# 17_-_HDMI_IN.net
KiCad netlist of a schematic drawn in Altium Designer
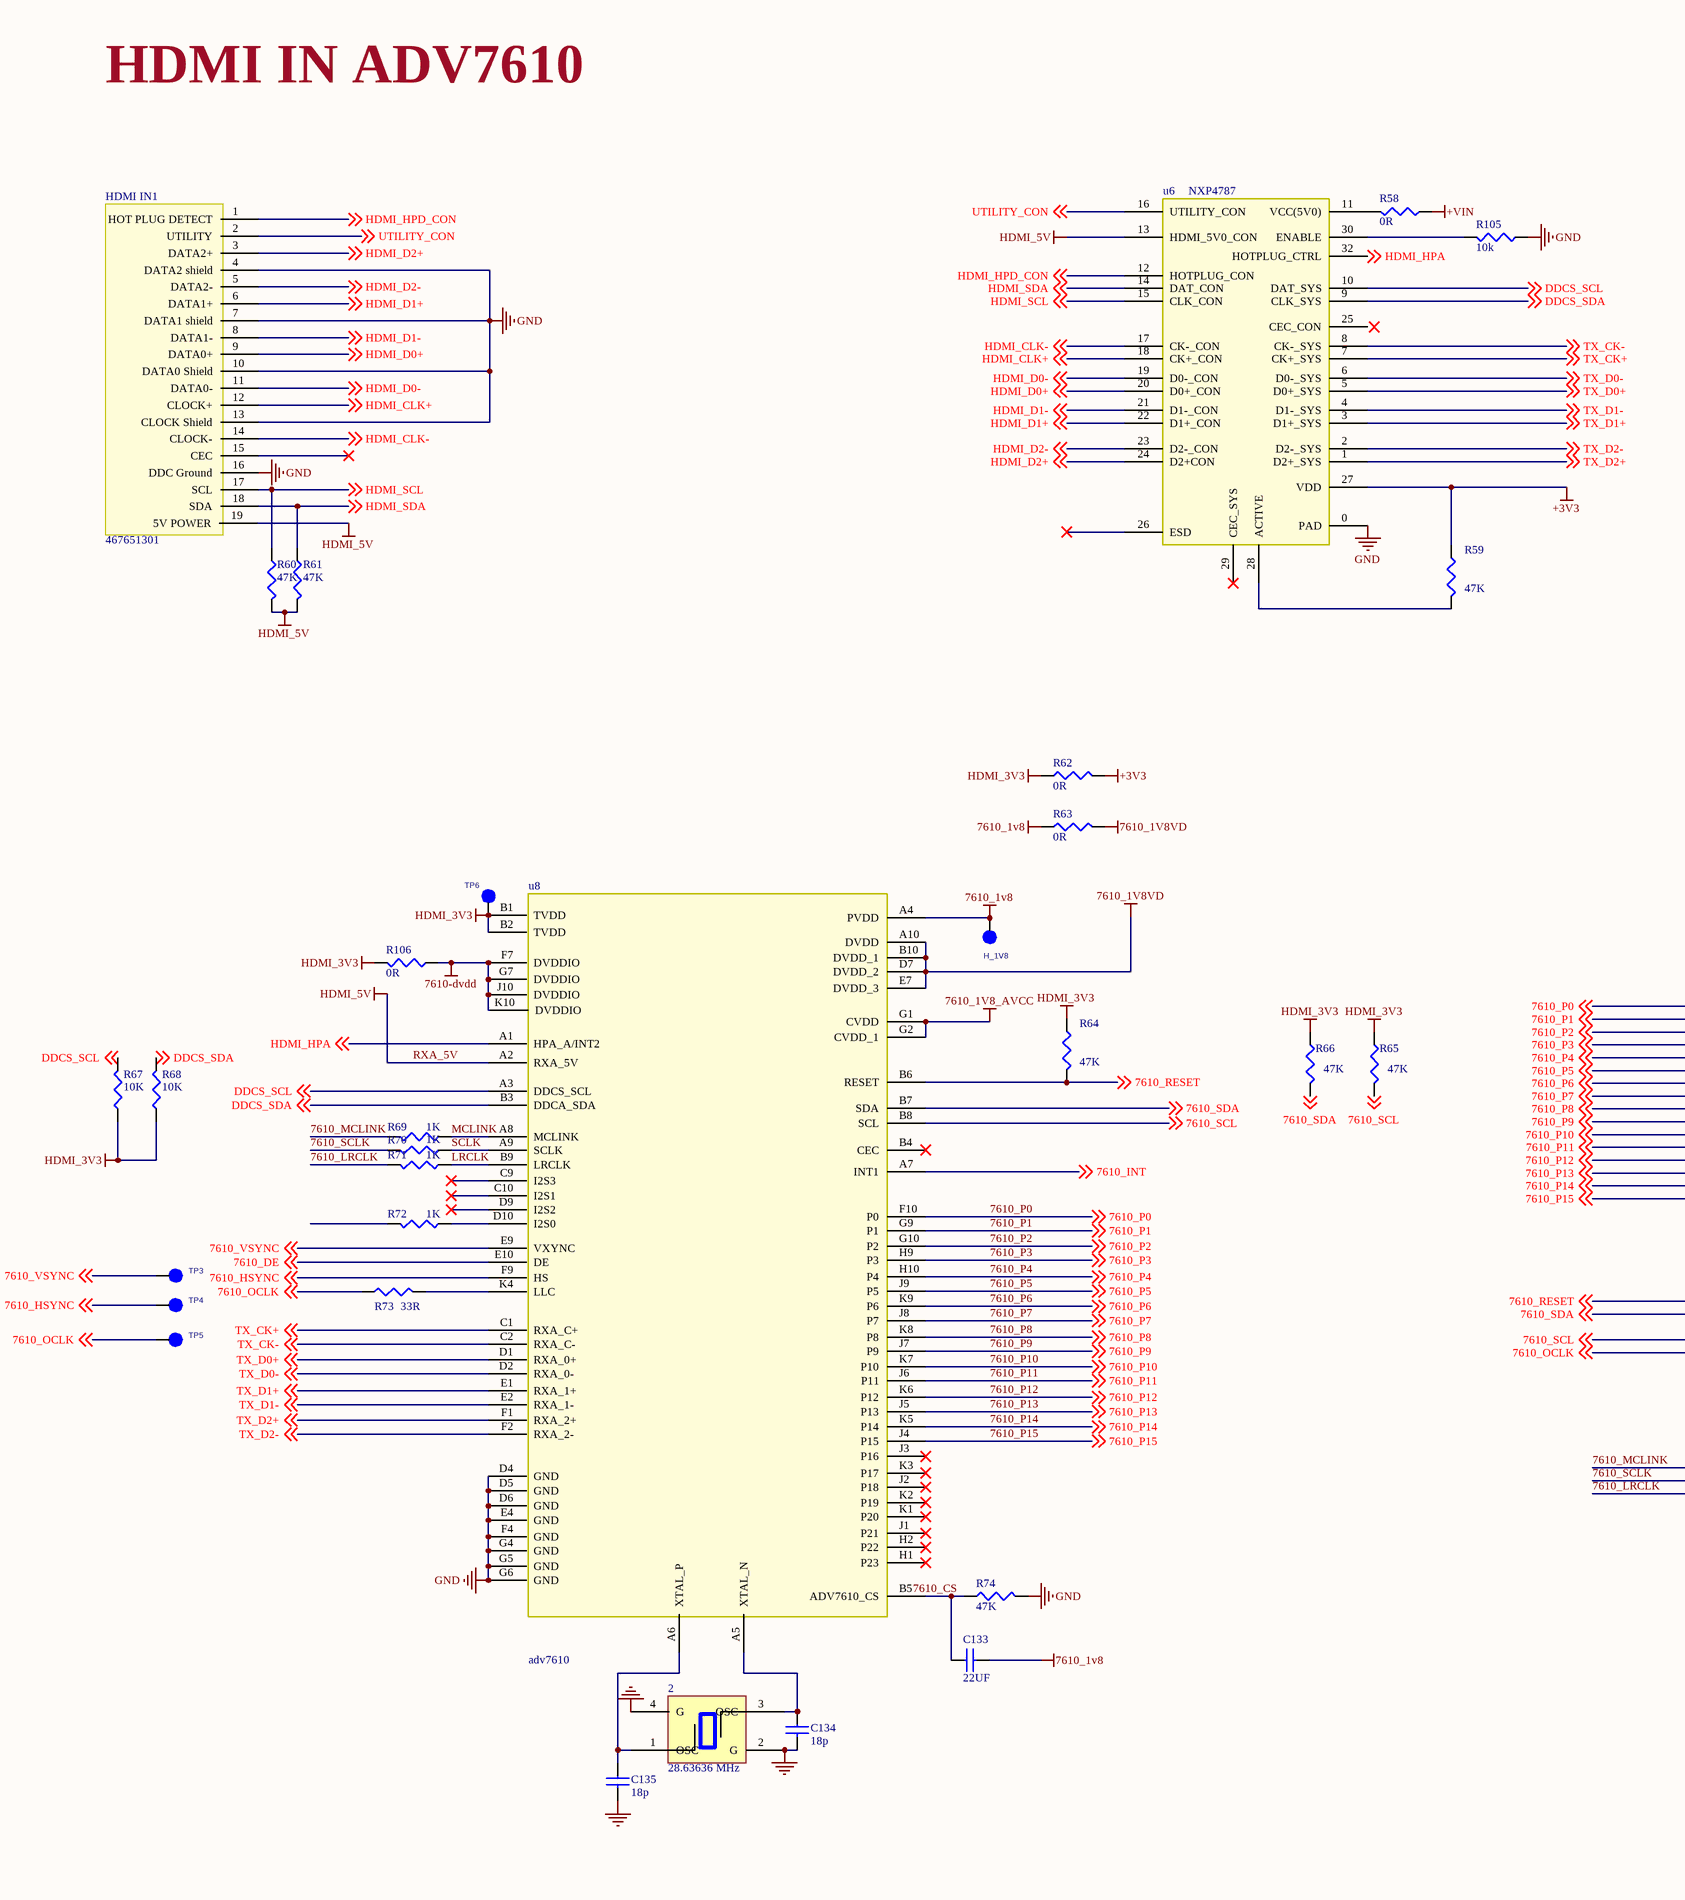
[diagram p0: [17] - HDMI_IN.SchDoc, left]
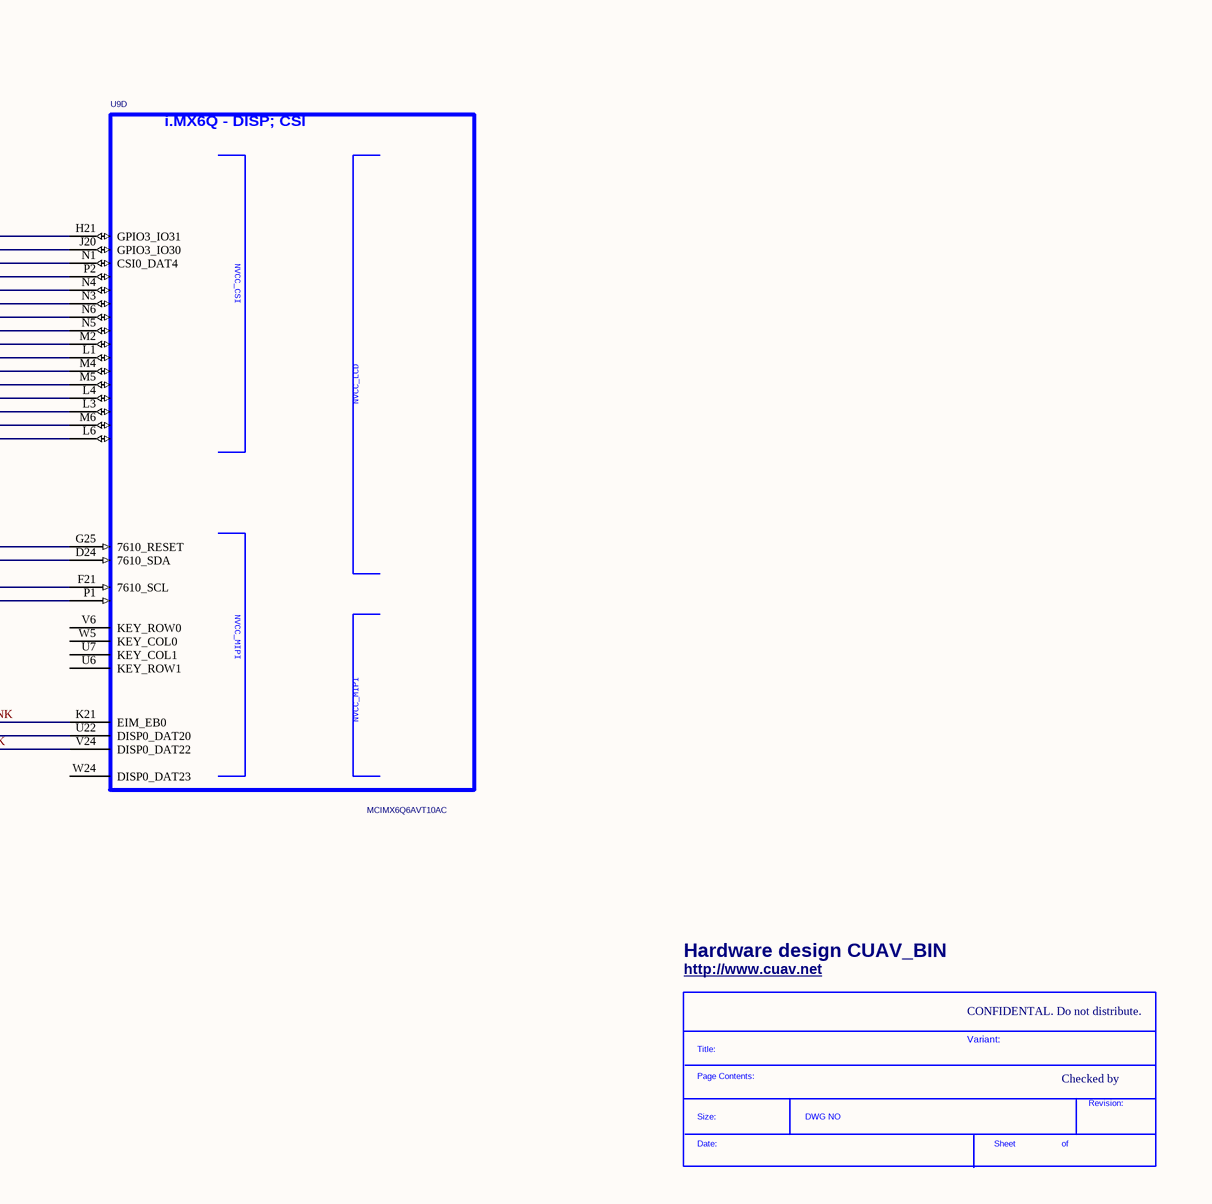
[diagram p1: [17] - HDMI_IN.SchDoc, right]

(export (version "E")
  (design (tool "Eeschema 10.0.6"))
  (components
    (comp (ref "*") (value "SDTitleBlock") (libsource (lib "*") (part "SDTitleBlock")))
    (comp (ref "2") (value "28.63636 MHz") (footprint "TSX-3225") (libsource (lib "hack") (part "TSX-3225")))
    (comp (ref "C133")
      (value "22UF")
      (footprint "0603C")
      (description "CAP CER 18PF 50V C0G 5% 0402")
      (fields
        (field (name "MANUFACTURER") "TDK Corporation")
        (field (name "MANUFACTURER PART NUMBER") "C1005C0G1H180J")
      )
      (libsource (lib "Integrated_Library_RF_FEB_2012") (part "C1005C0G1H180J"))
    )
    (comp (ref "C134")
      (value "18p")
      (footprint "0402cap")
      (description "CAP CER 18PF 50V C0G 5% 0402")
      (fields
        (field (name "MANUFACTURER") "TDK Corporation")
        (field (name "MANUFACTURER PART NUMBER") "C1005C0G1H180J")
      )
      (libsource (lib "Integrated_Library_RF_FEB_2012") (part "C1005C0G1H180J"))
    )
    (comp (ref "C135")
      (value "18p")
      (footprint "0402cap")
      (description "CAP CER 18PF 50V C0G 5% 0402")
      (fields
        (field (name "MANUFACTURER") "TDK Corporation")
        (field (name "MANUFACTURER PART NUMBER") "C1005C0G1H180J")
      )
      (libsource (lib "Integrated_Library_RF_FEB_2012") (part "C1005C0G1H180J"))
    )
    (comp (ref "HDMI IN1")
      (value "467651301")
      (footprint "467651301")
      (libsource (lib "hack") (part "467651301"))
    )
    (comp (ref "H_1V8")
      (value "H_3V3")
      (description "TEST POINT PAD 0.5MM DIA SMT, NO PART TO ORDER")
      (libsource (lib "*") (part "TESTLOOP"))
    )
    (comp (ref "R58")
      (value "0R")
      (footprint "R0402")
      (description "RES 1.00 OHM 1/16W 1% 0402 SM")
      (fields
        (field (name "MANUFACTURER") "Yageo")
        (field (name "MANUFACTURER PART NUMBER") "RC0402FR-071RL")
      )
      (libsource (lib "Integrated_Library_RF_FEB_2012") (part "RC0402FR-071RL"))
    )
    (comp (ref "R59")
      (value "47K")
      (footprint "R0402")
      (description "RES 1.00 OHM 1/16W 1% 0402 SM")
      (fields
        (field (name "MANUFACTURER") "Yageo")
        (field (name "MANUFACTURER PART NUMBER") "RC0402FR-071RL")
      )
      (libsource (lib "Integrated_Library_RF_FEB_2012") (part "RC0402FR-071RL"))
    )
    (comp (ref "R60")
      (value "47K")
      (footprint "R0402")
      (description "RES 1.00 OHM 1/16W 1% 0402 SM")
      (fields
        (field (name "MANUFACTURER") "Yageo")
        (field (name "MANUFACTURER PART NUMBER") "RC0402FR-071RL")
      )
      (libsource (lib "Integrated_Library_RF_FEB_2012") (part "RC0402FR-071RL"))
    )
    (comp (ref "R61")
      (value "47K")
      (footprint "R0402")
      (description "RES 1.00 OHM 1/16W 1% 0402 SM")
      (fields
        (field (name "MANUFACTURER") "Yageo")
        (field (name "MANUFACTURER PART NUMBER") "RC0402FR-071RL")
      )
      (libsource (lib "Integrated_Library_RF_FEB_2012") (part "RC0402FR-071RL"))
    )
    (comp (ref "R62")
      (value "0R")
      (footprint "R0402")
      (description "RES 1.00 OHM 1/16W 1% 0402 SM")
      (fields
        (field (name "MANUFACTURER") "Yageo")
        (field (name "MANUFACTURER PART NUMBER") "RC0402FR-071RL")
      )
      (libsource (lib "Integrated_Library_RF_FEB_2012") (part "RC0402FR-071RL"))
    )
    (comp (ref "R63")
      (value "0R")
      (footprint "R0402")
      (description "RES 1.00 OHM 1/16W 1% 0402 SM")
      (fields
        (field (name "MANUFACTURER") "Yageo")
        (field (name "MANUFACTURER PART NUMBER") "RC0402FR-071RL")
      )
      (libsource (lib "Integrated_Library_RF_FEB_2012") (part "RC0402FR-071RL"))
    )
    (comp (ref "R64")
      (value "47K")
      (footprint "R0402")
      (description "RES 1.00 OHM 1/16W 1% 0402 SM")
      (fields
        (field (name "MANUFACTURER") "Yageo")
        (field (name "MANUFACTURER PART NUMBER") "RC0402FR-071RL")
      )
      (libsource (lib "Integrated_Library_RF_FEB_2012") (part "RC0402FR-071RL"))
    )
    (comp (ref "R65")
      (value "47K")
      (footprint "R0402")
      (description "RES 39.0K OHM 1/16W 1% 0402 SMD")
      (fields
        (field (name "MANUFACTURER") "Yageo")
        (field (name "MANUFACTURER PART NUMBER") "RC0402FR-0739KL")
      )
      (libsource (lib "Integrated_Library_RF_FEB_2012") (part "RC0402FR-0739KL"))
    )
    (comp (ref "R66")
      (value "47K")
      (footprint "R0402")
      (description "RES 39.0K OHM 1/16W 1% 0402 SMD")
      (fields
        (field (name "MANUFACTURER") "Yageo")
        (field (name "MANUFACTURER PART NUMBER") "RC0402FR-0739KL")
      )
      (libsource (lib "Integrated_Library_RF_FEB_2012") (part "RC0402FR-0739KL"))
    )
    (comp (ref "R67")
      (value "10K")
      (footprint "R0402")
      (description "RES 1.00 OHM 1/16W 1% 0402 SM")
      (fields
        (field (name "MANUFACTURER") "Yageo")
        (field (name "MANUFACTURER PART NUMBER") "RC0402FR-071RL")
      )
      (libsource (lib "Integrated_Library_RF_FEB_2012") (part "RC0402FR-071RL"))
    )
    (comp (ref "R68")
      (value "10K")
      (footprint "R0402")
      (description "RES 1.00 OHM 1/16W 1% 0402 SM")
      (fields
        (field (name "MANUFACTURER") "Yageo")
        (field (name "MANUFACTURER PART NUMBER") "RC0402FR-071RL")
      )
      (libsource (lib "Integrated_Library_RF_FEB_2012") (part "RC0402FR-071RL"))
    )
    (comp (ref "R69")
      (value "1K")
      (footprint "R0402")
      (description "RES 1.00 OHM 1/16W 1% 0402 SM")
      (fields
        (field (name "MANUFACTURER") "Yageo")
        (field (name "MANUFACTURER PART NUMBER") "RC0402FR-071RL")
      )
      (libsource (lib "Integrated_Library_RF_FEB_2012") (part "RC0402FR-071RL"))
    )
    (comp (ref "R70")
      (value "1K")
      (footprint "R0402")
      (description "RES 1.00 OHM 1/16W 1% 0402 SM")
      (fields
        (field (name "MANUFACTURER") "Yageo")
        (field (name "MANUFACTURER PART NUMBER") "RC0402FR-071RL")
      )
      (libsource (lib "Integrated_Library_RF_FEB_2012") (part "RC0402FR-071RL"))
    )
    (comp (ref "R71")
      (value "1K")
      (footprint "R0402")
      (description "RES 1.00 OHM 1/16W 1% 0402 SM")
      (fields
        (field (name "MANUFACTURER") "Yageo")
        (field (name "MANUFACTURER PART NUMBER") "RC0402FR-071RL")
      )
      (libsource (lib "Integrated_Library_RF_FEB_2012") (part "RC0402FR-071RL"))
    )
    (comp (ref "R72")
      (value "1K")
      (footprint "R0402")
      (description "RES 1.00 OHM 1/16W 1% 0402 SM")
      (fields
        (field (name "MANUFACTURER") "Yageo")
        (field (name "MANUFACTURER PART NUMBER") "RC0402FR-071RL")
      )
      (libsource (lib "Integrated_Library_RF_FEB_2012") (part "RC0402FR-071RL"))
    )
    (comp (ref "R73")
      (value "33R")
      (footprint "R0402")
      (description "RES 1.00 OHM 1/16W 1% 0402 SM")
      (fields
        (field (name "MANUFACTURER") "Yageo")
        (field (name "MANUFACTURER PART NUMBER") "RC0402FR-071RL")
      )
      (libsource (lib "Integrated_Library_RF_FEB_2012") (part "RC0402FR-071RL"))
    )
    (comp (ref "R74")
      (value "47K")
      (footprint "R0402")
      (description "RES 1.00 OHM 1/16W 1% 0402 SM")
      (fields
        (field (name "MANUFACTURER") "Yageo")
        (field (name "MANUFACTURER PART NUMBER") "RC0402FR-071RL")
      )
      (libsource (lib "Integrated_Library_RF_FEB_2012") (part "RC0402FR-071RL"))
    )
    (comp (ref "R105")
      (value "10k")
      (footprint "R0402")
      (description "RES 1.00 OHM 1/16W 1% 0402 SM")
      (fields
        (field (name "MANUFACTURER") "Yageo")
        (field (name "MANUFACTURER PART NUMBER") "RC0402FR-071RL")
      )
      (libsource (lib "Integrated_Library_RF_FEB_2012") (part "RC0402FR-071RL"))
    )
    (comp (ref "R106")
      (value "0R")
      (footprint "R0402")
      (description "RES 1.00 OHM 1/16W 1% 0402 SM")
      (fields
        (field (name "MANUFACTURER") "Yageo")
        (field (name "MANUFACTURER PART NUMBER") "RC0402FR-071RL")
      )
      (libsource (lib "Integrated_Library_RF_FEB_2012") (part "RC0402FR-071RL"))
    )
    (comp (ref "TP3")
      (value "7610_VSYNC")
      (description "TEST POINT PAD 0.5MM DIA SMT, NO PART TO ORDER")
      (libsource (lib "*") (part "TESTLOOP"))
    )
    (comp (ref "TP4")
      (value "7610_HSYNC")
      (description "TEST POINT PAD 0.5MM DIA SMT, NO PART TO ORDER")
      (libsource (lib "*") (part "TESTLOOP"))
    )
    (comp (ref "TP5")
      (value "tpad_020")
      (description "TEST POINT PAD 0.5MM DIA SMT, NO PART TO ORDER")
      (libsource (lib "*") (part "TESTLOOP"))
    )
    (comp (ref "TP6")
      (value "H_3V3")
      (description "TEST POINT PAD 0.5MM DIA SMT, NO PART TO ORDER")
      (libsource (lib "*") (part "TESTLOOP"))
    )
    (comp (ref "u6") (value "NXP4787") (footprint "QFN32_1") (libsource (lib "hack") (part "NXP4787")))
    (comp (ref "u8") (value "adv7610") (footprint "BC-76") (libsource (lib "hack") (part "adv7610")))
    (comp (ref "U9")
      (value "MCIMX6Q6AVT10AC")
      (description "IC MCU MX6QUAD ARM CORTEX-A9 FCPBGA624")
      (libsource (lib "*") (part "PCIMX6Q6VV1A"))
    )
  )
  (nets
    (net (code "1") (name "+3V3") (class "Default")
      (node (ref "R59") (pin "1") (pinfunction "1_1") (pintype "passive"))
      (node (ref "R62") (pin "2") (pinfunction "2_2") (pintype "passive"))
      (node (ref "u6") (pin "27") (pinfunction "VDD_27") (pintype "passive"))
    )
    (net (code "2") (name "+VIN") (class "Default")
      (node (ref "R58") (pin "1") (pinfunction "1_1") (pintype "passive"))
    )
    (net (code "4") (name "/7610_LRCLK") (class "Default")
      (node (ref "R71") (pin "2") (pinfunction "2_2") (pintype "passive"))
      (node (ref "U9") (pin "V24") (pinfunction "DISP0_DAT22_V24") (pintype "passive"))
    )
    (net (code "5") (name "/7610_MCLINK") (class "Default")
      (node (ref "R69") (pin "2") (pinfunction "2_2") (pintype "passive"))
      (node (ref "U9") (pin "K21") (pinfunction "EIM_EB0_K21") (pintype "passive"))
    )
    (net (code "6") (name "/7610_SCLK") (class "Default")
      (node (ref "R70") (pin "2") (pinfunction "2_2") (pintype "passive"))
      (node (ref "U9") (pin "U22") (pinfunction "DISP0_DAT20_U22") (pintype "passive"))
    )
    (net (code "7") (name "/LRCLK") (class "Default")
      (node (ref "R71") (pin "1") (pinfunction "1_1") (pintype "passive"))
      (node (ref "u8") (pin "B9") (pinfunction "LRCLK_B9") (pintype "passive"))
    )
    (net (code "8") (name "/MCLINK") (class "Default")
      (node (ref "R69") (pin "1") (pinfunction "1_1") (pintype "passive"))
      (node (ref "u8") (pin "A8") (pinfunction "MCLINK_A8") (pintype "passive"))
    )
    (net (code "9") (name "/SCLK") (class "Default")
      (node (ref "R70") (pin "1") (pinfunction "1_1") (pintype "passive"))
      (node (ref "u8") (pin "A9") (pinfunction "SCLK_A9") (pintype "passive"))
    )
    (net (code "10") (name "7610-dvdd") (class "Default")
      (node (ref "R106") (pin "1") (pinfunction "1_1") (pintype "passive"))
      (node (ref "u8") (pin "F7") (pinfunction "DVDDIO_F7") (pintype "passive"))
      (node (ref "u8") (pin "G7") (pinfunction "DVDDIO_G7") (pintype "passive"))
      (node (ref "u8") (pin "J10") (pinfunction "DVDDIO_J10") (pintype "passive"))
      (node (ref "u8") (pin "K10") (pinfunction "DVDDIO_K10") (pintype "passive"))
    )
    (net (code "11") (name "7610_1V8VD") (class "Default")
      (node (ref "R63") (pin "2") (pinfunction "2_2") (pintype "passive"))
      (node (ref "u8") (pin "A10") (pinfunction "DVDD_A10") (pintype "passive"))
      (node (ref "u8") (pin "B10") (pinfunction "DVDD_1_B10") (pintype "passive"))
      (node (ref "u8") (pin "D7") (pinfunction "DVDD_2_D7") (pintype "passive"))
      (node (ref "u8") (pin "E7") (pinfunction "DVDD_3_E7") (pintype "passive"))
    )
    (net (code "12") (name "7610_1V8_AVCC") (class "Default")
      (node (ref "u8") (pin "G1") (pinfunction "CVDD_G1") (pintype "passive"))
      (node (ref "u8") (pin "G2") (pinfunction "CVDD_1_G2") (pintype "passive"))
    )
    (net (code "13") (name "7610_1v8") (class "Default")
      (node (ref "C133") (pin "2") (pinfunction "2_2") (pintype "passive"))
      (node (ref "H_1V8") (pin "1") (pinfunction "Pin1_1") (pintype "passive"))
      (node (ref "R63") (pin "1") (pinfunction "1_1") (pintype "passive"))
      (node (ref "u8") (pin "A4") (pinfunction "PVDD_A4") (pintype "passive"))
    )
    (net (code "14") (name "7610_DE") (class "Default")
      (node (ref "u8") (pin "E10") (pinfunction "DE_E10") (pintype "passive"))
    )
    (net (code "15") (name "7610_HSYNC") (class "Default")
      (node (ref "TP4") (pin "1") (pinfunction "Pin1_1") (pintype "passive"))
      (node (ref "u8") (pin "F9") (pinfunction "HS_F9") (pintype "passive"))
    )
    (net (code "16") (name "7610_INT") (class "Default")
      (node (ref "u8") (pin "A7") (pinfunction "INT1_A7") (pintype "passive"))
    )
    (net (code "17") (name "7610_OCLK") (class "Default")
      (node (ref "R73") (pin "1") (pinfunction "1_1") (pintype "passive"))
      (node (ref "TP5") (pin "1") (pinfunction "Pin1_1") (pintype "passive"))
      (node (ref "U9") (pin "P1") (pintype "input"))
    )
    (net (code "18") (name "7610_P0") (class "Default")
      (node (ref "U9") (pin "H21") (pinfunction "GPIO3_IO31_H21") (pintype "bidirectional"))
      (node (ref "u8") (pin "F10") (pinfunction "P0_F10") (pintype "passive"))
    )
    (net (code "19") (name "7610_P1") (class "Default")
      (node (ref "U9") (pin "J20") (pinfunction "GPIO3_IO30_J20") (pintype "bidirectional"))
      (node (ref "u8") (pin "G9") (pinfunction "P1_G9") (pintype "passive"))
    )
    (net (code "20") (name "7610_P2") (class "Default")
      (node (ref "U9") (pin "N1") (pinfunction "CSI0_DAT4_N1") (pintype "bidirectional"))
      (node (ref "u8") (pin "G10") (pinfunction "P2_G10") (pintype "passive"))
    )
    (net (code "21") (name "7610_P3") (class "Default")
      (node (ref "U9") (pin "P2") (pintype "bidirectional"))
      (node (ref "u8") (pin "H9") (pinfunction "P3_H9") (pintype "passive"))
    )
    (net (code "22") (name "7610_P4") (class "Default")
      (node (ref "U9") (pin "N4") (pintype "bidirectional"))
      (node (ref "u8") (pin "H10") (pinfunction "P4_H10") (pintype "passive"))
    )
    (net (code "23") (name "7610_P5") (class "Default")
      (node (ref "U9") (pin "N3") (pintype "bidirectional"))
      (node (ref "u8") (pin "J9") (pinfunction "P5_J9") (pintype "passive"))
    )
    (net (code "24") (name "7610_P6") (class "Default")
      (node (ref "U9") (pin "N6") (pintype "bidirectional"))
      (node (ref "u8") (pin "K9") (pinfunction "P6_K9") (pintype "passive"))
    )
    (net (code "25") (name "7610_P7") (class "Default")
      (node (ref "U9") (pin "N5") (pintype "bidirectional"))
      (node (ref "u8") (pin "J8") (pinfunction "P7_J8") (pintype "passive"))
    )
    (net (code "26") (name "7610_P8") (class "Default")
      (node (ref "U9") (pin "M2") (pintype "bidirectional"))
      (node (ref "u8") (pin "K8") (pinfunction "P8_K8") (pintype "passive"))
    )
    (net (code "27") (name "7610_P9") (class "Default")
      (node (ref "U9") (pin "L1") (pintype "bidirectional"))
      (node (ref "u8") (pin "J7") (pinfunction "P9_J7") (pintype "passive"))
    )
    (net (code "28") (name "7610_P10") (class "Default")
      (node (ref "U9") (pin "M4") (pintype "bidirectional"))
      (node (ref "u8") (pin "K7") (pinfunction "P10_K7") (pintype "passive"))
    )
    (net (code "29") (name "7610_P11") (class "Default")
      (node (ref "U9") (pin "M5") (pintype "bidirectional"))
      (node (ref "u8") (pin "J6") (pinfunction "P11_J6") (pintype "passive"))
    )
    (net (code "30") (name "7610_P12") (class "Default")
      (node (ref "U9") (pin "L4") (pintype "bidirectional"))
      (node (ref "u8") (pin "K6") (pinfunction "P12_K6") (pintype "passive"))
    )
    (net (code "31") (name "7610_P13") (class "Default")
      (node (ref "U9") (pin "L3") (pintype "bidirectional"))
      (node (ref "u8") (pin "J5") (pinfunction "P13_J5") (pintype "passive"))
    )
    (net (code "32") (name "7610_P14") (class "Default")
      (node (ref "U9") (pin "M6") (pintype "bidirectional"))
      (node (ref "u8") (pin "K5") (pinfunction "P14_K5") (pintype "passive"))
    )
    (net (code "33") (name "7610_P15") (class "Default")
      (node (ref "U9") (pin "L6") (pintype "bidirectional"))
      (node (ref "u8") (pin "J4") (pinfunction "P15_J4") (pintype "passive"))
    )
    (net (code "34") (name "7610_RESET") (class "Default")
      (node (ref "R64") (pin "2") (pinfunction "2_2") (pintype "passive"))
      (node (ref "U9") (pin "G25") (pinfunction "7610_RESET_G25") (pintype "input"))
      (node (ref "u8") (pin "B6") (pinfunction "RESET_B6") (pintype "passive"))
    )
    (net (code "35") (name "7610_SCL") (class "Default")
      (node (ref "R65") (pin "2") (pinfunction "2_2") (pintype "passive"))
      (node (ref "U9") (pin "F21") (pinfunction "7610_SCL_F21") (pintype "input"))
      (node (ref "u8") (pin "B8") (pinfunction "SCL_B8") (pintype "passive"))
    )
    (net (code "36") (name "7610_SDA") (class "Default")
      (node (ref "R66") (pin "2") (pinfunction "2_2") (pintype "passive"))
      (node (ref "U9") (pin "D24") (pinfunction "7610_SDA_D24") (pintype "input"))
      (node (ref "u8") (pin "B7") (pinfunction "SDA_B7") (pintype "passive"))
    )
    (net (code "37") (name "7610_VSYNC") (class "Default")
      (node (ref "TP3") (pin "1") (pinfunction "Pin1_1") (pintype "passive"))
      (node (ref "u8") (pin "E9") (pinfunction "VXYNC_E9") (pintype "passive"))
    )
    (net (code "38") (name "DDCS_SCL") (class "Default")
      (node (ref "R67") (pin "2") (pinfunction "2_2") (pintype "passive"))
      (node (ref "u6") (pin "10") (pinfunction "DAT_SYS_10") (pintype "passive"))
      (node (ref "u8") (pin "A3") (pinfunction "DDCS_SCL_A3") (pintype "passive"))
    )
    (net (code "39") (name "DDCS_SDA") (class "Default")
      (node (ref "R68") (pin "2") (pinfunction "2_2") (pintype "passive"))
      (node (ref "u6") (pin "9") (pinfunction "CLK_SYS_9") (pintype "passive"))
      (node (ref "u8") (pin "B3") (pinfunction "DDCA_SDA_B3") (pintype "passive"))
    )
    (net (code "40") (name "GND") (class "Default")
      (node (ref "2") (pin "2") (pinfunction "G_2") (pintype "passive"))
      (node (ref "2") (pin "4") (pinfunction "G_4") (pintype "passive"))
      (node (ref "C134") (pin "2") (pinfunction "2_2") (pintype "passive"))
      (node (ref "C135") (pin "2") (pinfunction "2_2") (pintype "passive"))
      (node (ref "HDMI IN1") (pin "10") (pinfunction "DATA0_Shield_10") (pintype "passive"))
      (node (ref "HDMI IN1") (pin "13") (pinfunction "CLOCK_Shield_13") (pintype "passive"))
      (node (ref "HDMI IN1") (pin "16") (pinfunction "DDC_Ground_16") (pintype "passive"))
      (node (ref "HDMI IN1") (pin "4") (pinfunction "DATA2_shield_4") (pintype "passive"))
      (node (ref "HDMI IN1") (pin "7") (pinfunction "DATA1_shield_7") (pintype "passive"))
      (node (ref "R105") (pin "1") (pinfunction "1_1") (pintype "passive"))
      (node (ref "R74") (pin "2") (pinfunction "2_2") (pintype "passive"))
      (node (ref "u6") (pin "0") (pinfunction "PAD_0") (pintype "passive"))
      (node (ref "u8") (pin "D4") (pinfunction "GND_D4") (pintype "passive"))
      (node (ref "u8") (pin "D5") (pinfunction "GND_D5") (pintype "passive"))
      (node (ref "u8") (pin "D6") (pinfunction "GND_D6") (pintype "passive"))
      (node (ref "u8") (pin "E4") (pinfunction "GND_E4") (pintype "passive"))
      (node (ref "u8") (pin "F4") (pinfunction "GND_F4") (pintype "passive"))
      (node (ref "u8") (pin "G4") (pinfunction "GND_G4") (pintype "passive"))
      (node (ref "u8") (pin "G5") (pinfunction "GND_G5") (pintype "passive"))
      (node (ref "u8") (pin "G6") (pinfunction "GND_G6") (pintype "passive"))
    )
    (net (code "41") (name "HDMI_3V3") (class "Default")
      (node (ref "R106") (pin "2") (pinfunction "2_2") (pintype "passive"))
      (node (ref "R62") (pin "1") (pinfunction "1_1") (pintype "passive"))
      (node (ref "R64") (pin "1") (pinfunction "1_1") (pintype "passive"))
      (node (ref "R65") (pin "1") (pinfunction "1_1") (pintype "passive"))
      (node (ref "R66") (pin "1") (pinfunction "1_1") (pintype "passive"))
      (node (ref "R67") (pin "1") (pinfunction "1_1") (pintype "passive"))
      (node (ref "R68") (pin "1") (pinfunction "1_1") (pintype "passive"))
      (node (ref "TP6") (pin "1") (pinfunction "Pin1_1") (pintype "passive"))
      (node (ref "u8") (pin "B1") (pinfunction "TVDD_B1") (pintype "passive"))
      (node (ref "u8") (pin "B2") (pinfunction "TVDD_B2") (pintype "passive"))
    )
    (net (code "42") (name "HDMI_5V") (class "Default")
      (node (ref "HDMI IN1") (pin "19") (pinfunction "5V_POWER_19") (pintype "passive"))
      (node (ref "R60") (pin "2") (pinfunction "2_2") (pintype "passive"))
      (node (ref "R61") (pin "2") (pinfunction "2_2") (pintype "passive"))
      (node (ref "u6") (pin "13") (pinfunction "HDMI_5V0_CON_13") (pintype "passive"))
      (node (ref "u8") (pin "A2") (pinfunction "RXA_5V_A2") (pintype "passive"))
    )
    (net (code "43") (name "HDMI_CLK+") (class "Default")
      (node (ref "HDMI IN1") (pin "12") (pinfunction "CLOCK+_12") (pintype "passive"))
      (node (ref "u6") (pin "18") (pinfunction "CK+_CON_18") (pintype "passive"))
    )
    (net (code "44") (name "HDMI_CLK-") (class "Default")
      (node (ref "HDMI IN1") (pin "14") (pinfunction "CLOCK-_14") (pintype "passive"))
      (node (ref "u6") (pin "17") (pinfunction "CK-_CON_17") (pintype "passive"))
    )
    (net (code "45") (name "HDMI_D0+") (class "Default")
      (node (ref "HDMI IN1") (pin "9") (pinfunction "DATA0+_9") (pintype "passive"))
      (node (ref "u6") (pin "20") (pinfunction "D0+_CON_20") (pintype "passive"))
    )
    (net (code "46") (name "HDMI_D0-") (class "Default")
      (node (ref "HDMI IN1") (pin "11") (pinfunction "DATA0-_11") (pintype "passive"))
      (node (ref "u6") (pin "19") (pinfunction "D0-_CON_19") (pintype "passive"))
    )
    (net (code "47") (name "HDMI_D1+") (class "Default")
      (node (ref "HDMI IN1") (pin "6") (pinfunction "DATA1+_6") (pintype "passive"))
      (node (ref "u6") (pin "22") (pinfunction "D1+_CON_22") (pintype "passive"))
    )
    (net (code "48") (name "HDMI_D1-") (class "Default")
      (node (ref "HDMI IN1") (pin "8") (pinfunction "DATA1-_8") (pintype "passive"))
      (node (ref "u6") (pin "21") (pinfunction "D1-_CON_21") (pintype "passive"))
    )
    (net (code "49") (name "HDMI_D2+") (class "Default")
      (node (ref "HDMI IN1") (pin "3") (pinfunction "DATA2+_3") (pintype "passive"))
      (node (ref "u6") (pin "24") (pinfunction "D2+CON_24") (pintype "passive"))
    )
    (net (code "50") (name "HDMI_D2-") (class "Default")
      (node (ref "HDMI IN1") (pin "5") (pinfunction "DATA2-_5") (pintype "passive"))
      (node (ref "u6") (pin "23") (pinfunction "D2-_CON_23") (pintype "passive"))
    )
    (net (code "51") (name "HDMI_HPA") (class "Default")
      (node (ref "u6") (pin "32") (pinfunction "HOTPLUG_CTRL_32") (pintype "passive"))
      (node (ref "u8") (pin "A1") (pinfunction "HPA_A/INT2_A1") (pintype "passive"))
    )
    (net (code "52") (name "HDMI_HPD_CON") (class "Default")
      (node (ref "HDMI IN1") (pin "1") (pinfunction "HOT_PLUG_DETECT_1") (pintype "passive"))
      (node (ref "u6") (pin "12") (pinfunction "HOTPLUG_CON_12") (pintype "passive"))
    )
    (net (code "53") (name "HDMI_SCL") (class "Default")
      (node (ref "HDMI IN1") (pin "17") (pinfunction "SCL_17") (pintype "passive"))
      (node (ref "R60") (pin "1") (pinfunction "1_1") (pintype "passive"))
      (node (ref "u6") (pin "15") (pinfunction "CLK_CON_15") (pintype "passive"))
    )
    (net (code "54") (name "HDMI_SDA") (class "Default")
      (node (ref "HDMI IN1") (pin "18") (pinfunction "SDA_18") (pintype "passive"))
      (node (ref "R61") (pin "1") (pinfunction "1_1") (pintype "passive"))
      (node (ref "u6") (pin "14") (pinfunction "DAT_CON_14") (pintype "passive"))
    )
    (net (code "55") (name "Net-(u6-ACTIVE)") (class "Default")
      (node (ref "R59") (pin "2") (pinfunction "2_2") (pintype "passive"))
      (node (ref "u6") (pin "28") (pinfunction "ACTIVE_28") (pintype "passive"))
    )
    (net (code "56") (name "Net-(u6-ENABLE)") (class "Default")
      (node (ref "R105") (pin "2") (pinfunction "2_2") (pintype "passive"))
      (node (ref "u6") (pin "30") (pinfunction "ENABLE_30") (pintype "passive"))
    )
    (net (code "57") (name "Net-(u6-VCC(5V0))") (class "Default")
      (node (ref "R58") (pin "2") (pinfunction "2_2") (pintype "passive"))
      (node (ref "u6") (pin "11") (pinfunction "VCC(5V0)_11") (pintype "passive"))
    )
    (net (code "58") (name "Net-(u8-ADV7610_CS)") (class "Default")
      (node (ref "C133") (pin "1") (pinfunction "1_1") (pintype "passive"))
      (node (ref "R74") (pin "1") (pinfunction "1_1") (pintype "passive"))
      (node (ref "u8") (pin "B5") (pinfunction "ADV7610_CS_B5") (pintype "passive"))
    )
    (net (code "59") (name "Net-(u8-I2S0)") (class "Default")
      (node (ref "R72") (pin "1") (pinfunction "1_1") (pintype "passive"))
      (node (ref "u8") (pin "D10") (pinfunction "I2S0_D10") (pintype "passive"))
    )
    (net (code "60") (name "Net-(u8-LLC)") (class "Default")
      (node (ref "R73") (pin "2") (pinfunction "2_2") (pintype "passive"))
      (node (ref "u8") (pin "K4") (pinfunction "LLC_K4") (pintype "passive"))
    )
    (net (code "61") (name "Net-(u8-XTAL_N)") (class "Default")
      (node (ref "2") (pin "3") (pinfunction "OSC_3") (pintype "passive"))
      (node (ref "C134") (pin "1") (pinfunction "1_1") (pintype "passive"))
      (node (ref "u8") (pin "A5") (pinfunction "XTAL_N_A5") (pintype "passive"))
    )
    (net (code "62") (name "Net-(u8-XTAL_P)") (class "Default")
      (node (ref "2") (pin "1") (pinfunction "OSC_1") (pintype "passive"))
      (node (ref "C135") (pin "1") (pinfunction "1_1") (pintype "passive"))
      (node (ref "u8") (pin "A6") (pinfunction "XTAL_P_A6") (pintype "passive"))
    )
    (net (code "63") (name "TX_CK+") (class "Default")
      (node (ref "u6") (pin "7") (pinfunction "CK+_SYS_7") (pintype "passive"))
      (node (ref "u8") (pin "C1") (pinfunction "RXA_C+_C1") (pintype "passive"))
    )
    (net (code "64") (name "TX_CK-") (class "Default")
      (node (ref "u6") (pin "8") (pinfunction "CK-_SYS_8") (pintype "passive"))
      (node (ref "u8") (pin "C2") (pinfunction "RXA_C-_C2") (pintype "passive"))
    )
    (net (code "65") (name "TX_D0+") (class "Default")
      (node (ref "u6") (pin "5") (pinfunction "D0+_SYS_5") (pintype "passive"))
      (node (ref "u8") (pin "D1") (pinfunction "RXA_0+_D1") (pintype "passive"))
    )
    (net (code "66") (name "TX_D0-") (class "Default")
      (node (ref "u6") (pin "6") (pinfunction "D0-_SYS_6") (pintype "passive"))
      (node (ref "u8") (pin "D2") (pinfunction "RXA_0-_D2") (pintype "passive"))
    )
    (net (code "67") (name "TX_D1+") (class "Default")
      (node (ref "u6") (pin "3") (pinfunction "D1+_SYS_3") (pintype "passive"))
      (node (ref "u8") (pin "E1") (pinfunction "RXA_1+_E1") (pintype "passive"))
    )
    (net (code "68") (name "TX_D1-") (class "Default")
      (node (ref "u6") (pin "4") (pinfunction "D1-_SYS_4") (pintype "passive"))
      (node (ref "u8") (pin "E2") (pinfunction "RXA_1-_E2") (pintype "passive"))
    )
    (net (code "69") (name "TX_D2+") (class "Default")
      (node (ref "u6") (pin "1") (pinfunction "D2+_SYS_1") (pintype "passive"))
      (node (ref "u8") (pin "F1") (pinfunction "RXA_2+_F1") (pintype "passive"))
    )
    (net (code "70") (name "TX_D2-") (class "Default")
      (node (ref "u6") (pin "2") (pinfunction "D2-_SYS_2") (pintype "passive"))
      (node (ref "u8") (pin "F2") (pinfunction "RXA_2-_F2") (pintype "passive"))
    )
    (net (code "71") (name "UTILITY_CON") (class "Default")
      (node (ref "HDMI IN1") (pin "2") (pinfunction "UTILITY_2") (pintype "passive"))
      (node (ref "u6") (pin "16") (pinfunction "UTILITY_CON_16") (pintype "passive"))
    )
    (net (code "72") (name "unconnected-(HDMI IN1-CEC-Pad15)") (class "Default")
      (node (ref "HDMI IN1") (pin "15") (pinfunction "CEC_15") (pintype "passive+no_connect"))
    )
    (net (code "73") (name "unconnected-(R72-Pad2)") (class "Default")
      (node (ref "R72") (pin "2") (pinfunction "2_2") (pintype "passive"))
    )
    (net (code "74") (name "unconnected-(U9D-DISP0_DAT23-PadW24)") (class "Default")
      (node (ref "U9") (pin "W24") (pinfunction "DISP0_DAT23_W24") (pintype "passive"))
    )
    (net (code "75") (name "unconnected-(U9D-KEY_COL0-PadW5)") (class "Default")
      (node (ref "U9") (pin "W5") (pinfunction "KEY_COL0_W5") (pintype "passive"))
    )
    (net (code "76") (name "unconnected-(U9D-KEY_COL1-PadU7)") (class "Default")
      (node (ref "U9") (pin "U7") (pinfunction "KEY_COL1_U7") (pintype "passive"))
    )
    (net (code "77") (name "unconnected-(U9D-KEY_ROW0-PadV6)") (class "Default")
      (node (ref "U9") (pin "V6") (pinfunction "KEY_ROW0_V6") (pintype "passive"))
    )
    (net (code "78") (name "unconnected-(U9D-KEY_ROW1-PadU6)") (class "Default")
      (node (ref "U9") (pin "U6") (pinfunction "KEY_ROW1_U6") (pintype "passive"))
    )
    (net (code "79") (name "unconnected-(u6-CEC_CON-Pad25)") (class "Default")
      (node (ref "u6") (pin "25") (pinfunction "CEC_CON_25") (pintype "passive"))
    )
    (net (code "80") (name "unconnected-(u6-CEC_SYS-Pad29)") (class "Default")
      (node (ref "u6") (pin "29") (pinfunction "CEC_SYS_29") (pintype "passive+no_connect"))
    )
    (net (code "81") (name "unconnected-(u6-ESD-Pad26)") (class "Default")
      (node (ref "u6") (pin "26") (pinfunction "ESD_26") (pintype "passive+no_connect"))
    )
    (net (code "82") (name "unconnected-(u8-CEC-PadB4)") (class "Default")
      (node (ref "u8") (pin "B4") (pinfunction "CEC_B4") (pintype "passive+no_connect"))
    )
    (net (code "83") (name "unconnected-(u8-I2S1-PadC10)") (class "Default")
      (node (ref "u8") (pin "C10") (pinfunction "I2S1_C10") (pintype "passive+no_connect"))
    )
    (net (code "84") (name "unconnected-(u8-I2S2-PadD9)") (class "Default")
      (node (ref "u8") (pin "D9") (pinfunction "I2S2_D9") (pintype "passive+no_connect"))
    )
    (net (code "85") (name "unconnected-(u8-I2S3-PadC9)") (class "Default")
      (node (ref "u8") (pin "C9") (pinfunction "I2S3_C9") (pintype "passive+no_connect"))
    )
    (net (code "86") (name "unconnected-(u8-P16-PadJ3)") (class "Default")
      (node (ref "u8") (pin "J3") (pinfunction "P16_J3") (pintype "passive+no_connect"))
    )
    (net (code "87") (name "unconnected-(u8-P17-PadK3)") (class "Default")
      (node (ref "u8") (pin "K3") (pinfunction "P17_K3") (pintype "passive+no_connect"))
    )
    (net (code "88") (name "unconnected-(u8-P18-PadJ2)") (class "Default")
      (node (ref "u8") (pin "J2") (pinfunction "P18_J2") (pintype "passive+no_connect"))
    )
    (net (code "89") (name "unconnected-(u8-P19-PadK2)") (class "Default")
      (node (ref "u8") (pin "K2") (pinfunction "P19_K2") (pintype "passive+no_connect"))
    )
    (net (code "90") (name "unconnected-(u8-P20-PadK1)") (class "Default")
      (node (ref "u8") (pin "K1") (pinfunction "P20_K1") (pintype "passive+no_connect"))
    )
    (net (code "91") (name "unconnected-(u8-P21-PadJ1)") (class "Default")
      (node (ref "u8") (pin "J1") (pinfunction "P21_J1") (pintype "passive+no_connect"))
    )
    (net (code "92") (name "unconnected-(u8-P22-PadH2)") (class "Default")
      (node (ref "u8") (pin "H2") (pinfunction "P22_H2") (pintype "passive+no_connect"))
    )
    (net (code "93") (name "unconnected-(u8-P23-PadH1)") (class "Default")
      (node (ref "u8") (pin "H1") (pinfunction "P23_H1") (pintype "passive+no_connect"))
    )
  )
)
